# Cutter_V1B.net
KiCad netlist of a schematic drawn in EAGLE
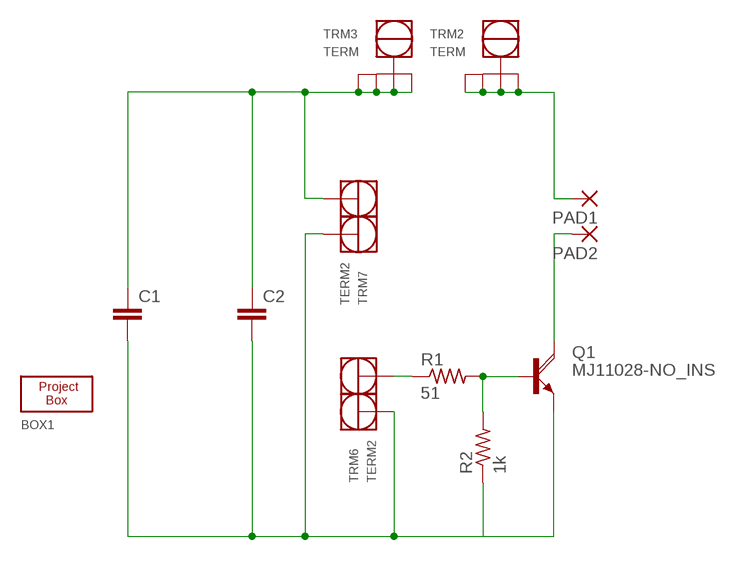
[diagram p0: schematic, sheet 1]

(export (version "E")
  (design (tool "Eeschema 10.0.6"))
  (components
    (comp (ref "BOX1")
      (value "RS_BOX_3IN")
      (footprint "eagle-import:RS_BOX_OUTLINE_3IN")
      (libsource (lib "eagle-import") (part "RS_BOX_3IN"))
    )
    (comp (ref "C1")
      (value "C1400X850")
      (footprint "eagle-import:SUPERCAP1.4_0.85H")
      (libsource (lib "eagle-import") (part "C1400X850"))
    )
    (comp (ref "C2")
      (value "C1400X850")
      (footprint "eagle-import:SUPERCAP1.4_0.85H")
      (libsource (lib "eagle-import") (part "C1400X850"))
    )
    (comp (ref "PAD1")
      (value "2,15/1,0")
      (footprint "eagle-import:2,15_1,0")
      (libsource (lib "eagle-import") (part "2,15/1,0"))
    )
    (comp (ref "PAD2")
      (value "2,15/1,0")
      (footprint "eagle-import:2,15_1,0")
      (libsource (lib "eagle-import") (part "2,15/1,0"))
    )
    (comp (ref "Q1")
      (value "MJ11028-NO_INS")
      (footprint "eagle-import:TO-3-NO_INSULATOR")
      (libsource (lib "eagle-import") (part "MJ11028-NO_INS"))
    )
    (comp (ref "R1")
      (value "51")
      (footprint "eagle-import:0207_10")
      (libsource (lib "eagle-import") (part "R-US_0207/10"))
    )
    (comp (ref "R2")
      (value "1k")
      (footprint "eagle-import:0207_10")
      (libsource (lib "eagle-import") (part "R-US_0207/10"))
    )
    (comp (ref "TRM2")
      (value "TERM")
      (footprint "eagle-import:SCREWTERM-300MILSQ")
      (libsource (lib "eagle-import") (part "TERM"))
    )
    (comp (ref "TRM3")
      (value "TERM")
      (footprint "eagle-import:SCREWTERM-300MILSQ")
      (libsource (lib "eagle-import") (part "TERM"))
    )
    (comp (ref "TRM6")
      (value "TERM2")
      (footprint "eagle-import:SCREWTERMBLK-DUAL")
      (libsource (lib "eagle-import") (part "TERM2"))
    )
    (comp (ref "TRM7")
      (value "TERM2")
      (footprint "eagle-import:SCREWTERMBLK-DUAL")
      (libsource (lib "eagle-import") (part "TERM2"))
    )
  )
  (nets
    (net (code "1") (name "Net-(C1-1)") (class "Default")
      (node (ref "C1") (pin "P$1") (pinfunction "1_P$1") (pintype "passive"))
      (node (ref "C2") (pin "P$1") (pinfunction "1_P$1") (pintype "passive"))
      (node (ref "TRM3") (pin "P$1") (pinfunction "P1_P$1") (pintype "passive"))
      (node (ref "TRM3") (pin "P$2") (pinfunction "P2_P$2") (pintype "passive"))
      (node (ref "TRM3") (pin "P$3") (pinfunction "P3_P$3") (pintype "passive"))
      (node (ref "TRM3") (pin "P$4") (pinfunction "P4_P$4") (pintype "passive"))
      (node (ref "TRM7") (pin "P$2") (pinfunction "P2_P$2") (pintype "passive"))
    )
    (net (code "2") (name "Net-(C1-2)") (class "Default")
      (node (ref "C1") (pin "P$2") (pinfunction "2_P$2") (pintype "passive"))
      (node (ref "C2") (pin "P$2") (pinfunction "2_P$2") (pintype "passive"))
      (node (ref "Q1") (pin "E") (pinfunction "E_E") (pintype "passive"))
      (node (ref "R2") (pin "1") (pinfunction "1_1") (pintype "passive"))
      (node (ref "TRM6") (pin "P$1") (pinfunction "P1_P$1") (pintype "passive"))
      (node (ref "TRM7") (pin "P$1") (pinfunction "P1_P$1") (pintype "passive"))
    )
    (net (code "3") (name "Net-(PAD1-P)") (class "Default")
      (node (ref "PAD1") (pin "1") (pinfunction "P_1") (pintype "passive"))
      (node (ref "TRM2") (pin "P$1") (pinfunction "P1_P$1") (pintype "passive"))
      (node (ref "TRM2") (pin "P$2") (pinfunction "P2_P$2") (pintype "passive"))
      (node (ref "TRM2") (pin "P$3") (pinfunction "P3_P$3") (pintype "passive"))
      (node (ref "TRM2") (pin "P$4") (pinfunction "P4_P$4") (pintype "passive"))
    )
    (net (code "4") (name "Net-(PAD2-P)") (class "Default")
      (node (ref "PAD2") (pin "1") (pinfunction "P_1") (pintype "passive"))
      (node (ref "Q1") (pin "C") (pinfunction "C_C") (pintype "passive"))
      (node (ref "Q1") (pin "C1") (pinfunction "C_C1") (pintype "passive"))
    )
    (net (code "5") (name "Net-(Q1-PadB)") (class "Default")
      (node (ref "Q1") (pin "B") (pinfunction "B_B") (pintype "passive"))
      (node (ref "R1") (pin "2") (pinfunction "2_2") (pintype "passive"))
      (node (ref "R2") (pin "2") (pinfunction "2_2") (pintype "passive"))
    )
    (net (code "6") (name "Net-(TRM6-P2)") (class "Default")
      (node (ref "R1") (pin "1") (pinfunction "1_1") (pintype "passive"))
      (node (ref "TRM6") (pin "P$2") (pinfunction "P2_P$2") (pintype "passive"))
    )
  )
)
